# TemperatureSensor.net
KiCad netlist of a schematic drawn in EAGLE
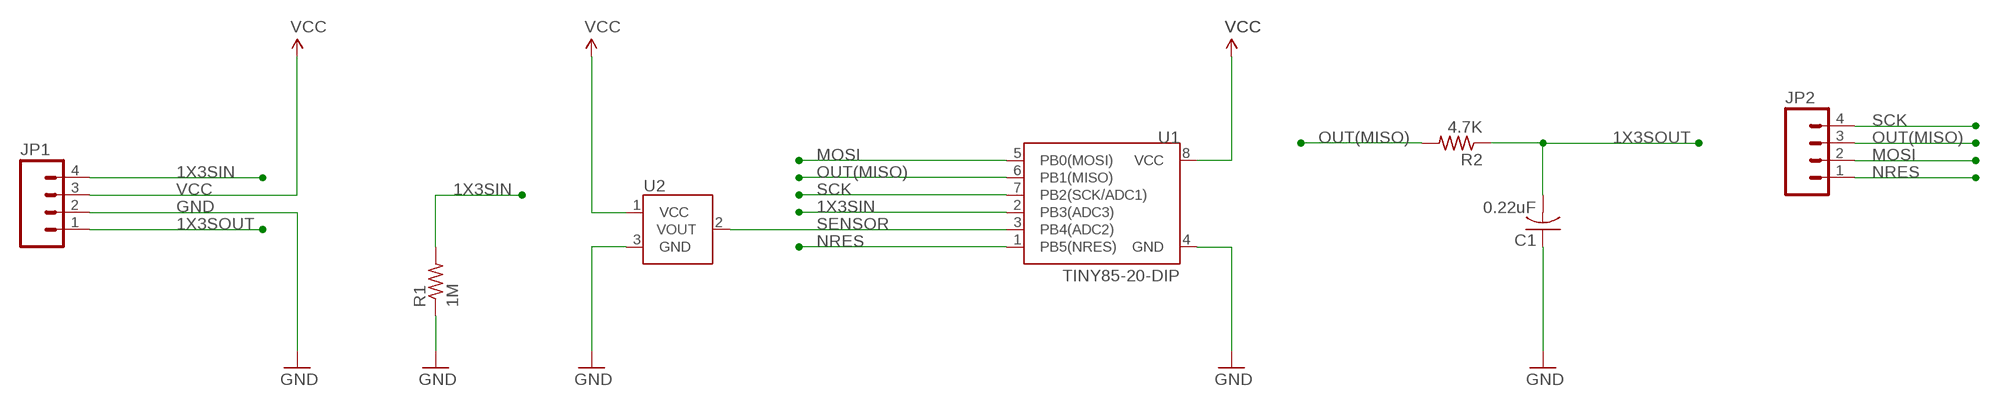
[diagram p0: schematic, sheet 1]

(export (version "E")
  (design (tool "Eeschema 10.0.6"))
  (components
    (comp (ref "C1")
      (value "0.22uF")
      (footprint "eagle-import:C0402")
      (libsource (lib "eagle-import") (part "C-USC0402"))
    )
    (comp (ref "JP1")
      (value "M04PTH")
      (footprint "eagle-import:1X04")
      (libsource (lib "eagle-import") (part "M04PTH"))
    )
    (comp (ref "JP2")
      (value "M04PTH")
      (footprint "eagle-import:1X04")
      (libsource (lib "eagle-import") (part "M04PTH"))
    )
    (comp (ref "R1")
      (value "1M")
      (footprint "eagle-import:R0603")
      (libsource (lib "eagle-import") (part "R-US_R0603"))
    )
    (comp (ref "R2")
      (value "4.7K")
      (footprint "eagle-import:R0603")
      (libsource (lib "eagle-import") (part "R-US_R0603"))
    )
    (comp (ref "U1")
      (value "TINY85-20-DIP")
      (footprint "eagle-import:DIP08")
      (libsource (lib "eagle-import") (part "ATTINY45TINY85-20-DIP"))
    )
    (comp (ref "U2")
      (value "TMP36GT9")
      (footprint "eagle-import:TO-92")
      (libsource (lib "eagle-import") (part "TMP36GT9"))
    )
  )
  (nets
    (net (code "1") (name "/1X3SIN") (class "Default")
      (node (ref "JP1") (pin "4") (pinfunction "4_4") (pintype "passive"))
      (node (ref "R1") (pin "2") (pinfunction "2_2") (pintype "passive"))
      (node (ref "U1") (pin "2") (pinfunction "PB3(ADC3)_2") (pintype "bidirectional"))
    )
    (net (code "2") (name "/1X3SOUT") (class "Default")
      (node (ref "C1") (pin "2") (pinfunction "2_2") (pintype "passive"))
      (node (ref "JP1") (pin "1") (pinfunction "1_1") (pintype "passive"))
      (node (ref "R2") (pin "1") (pinfunction "1_1") (pintype "passive"))
    )
    (net (code "3") (name "/MOSI") (class "Default")
      (node (ref "JP2") (pin "2") (pinfunction "2_2") (pintype "passive"))
      (node (ref "U1") (pin "5") (pinfunction "PB0(MOSI)_5") (pintype "bidirectional"))
    )
    (net (code "4") (name "/NRES") (class "Default")
      (node (ref "JP2") (pin "1") (pinfunction "1_1") (pintype "passive"))
      (node (ref "U1") (pin "1") (pinfunction "PB5(NRES)_1") (pintype "bidirectional"))
    )
    (net (code "5") (name "/OUT(MISO)") (class "Default")
      (node (ref "JP2") (pin "3") (pinfunction "3_3") (pintype "passive"))
      (node (ref "R2") (pin "2") (pinfunction "2_2") (pintype "passive"))
      (node (ref "U1") (pin "6") (pinfunction "PB1(MISO)_6") (pintype "bidirectional"))
    )
    (net (code "6") (name "/SCK") (class "Default")
      (node (ref "JP2") (pin "4") (pinfunction "4_4") (pintype "passive"))
      (node (ref "U1") (pin "7") (pinfunction "PB2(SCK/ADC1)_7") (pintype "bidirectional"))
    )
    (net (code "7") (name "/SENSOR") (class "Default")
      (node (ref "U1") (pin "3") (pinfunction "PB4(ADC2)_3") (pintype "bidirectional"))
      (node (ref "U2") (pin "2") (pinfunction "VOUT_2") (pintype "bidirectional"))
    )
    (net (code "8") (name "GND") (class "Default")
      (node (ref "C1") (pin "1") (pinfunction "1_1") (pintype "passive"))
      (node (ref "JP1") (pin "2") (pinfunction "2_2") (pintype "passive"))
      (node (ref "R1") (pin "1") (pinfunction "1_1") (pintype "passive"))
      (node (ref "U1") (pin "4") (pinfunction "GND_4") (pintype "bidirectional"))
      (node (ref "U2") (pin "3") (pinfunction "GND_3") (pintype "bidirectional"))
    )
    (net (code "9") (name "VCC") (class "Default")
      (node (ref "JP1") (pin "3") (pinfunction "3_3") (pintype "passive"))
      (node (ref "U1") (pin "8") (pinfunction "VCC_8") (pintype "bidirectional"))
      (node (ref "U2") (pin "1") (pinfunction "VCC_1") (pintype "bidirectional"))
    )
  )
)
